# Warble_PitchBird.net
KiCad netlist of a schematic drawn in EAGLE
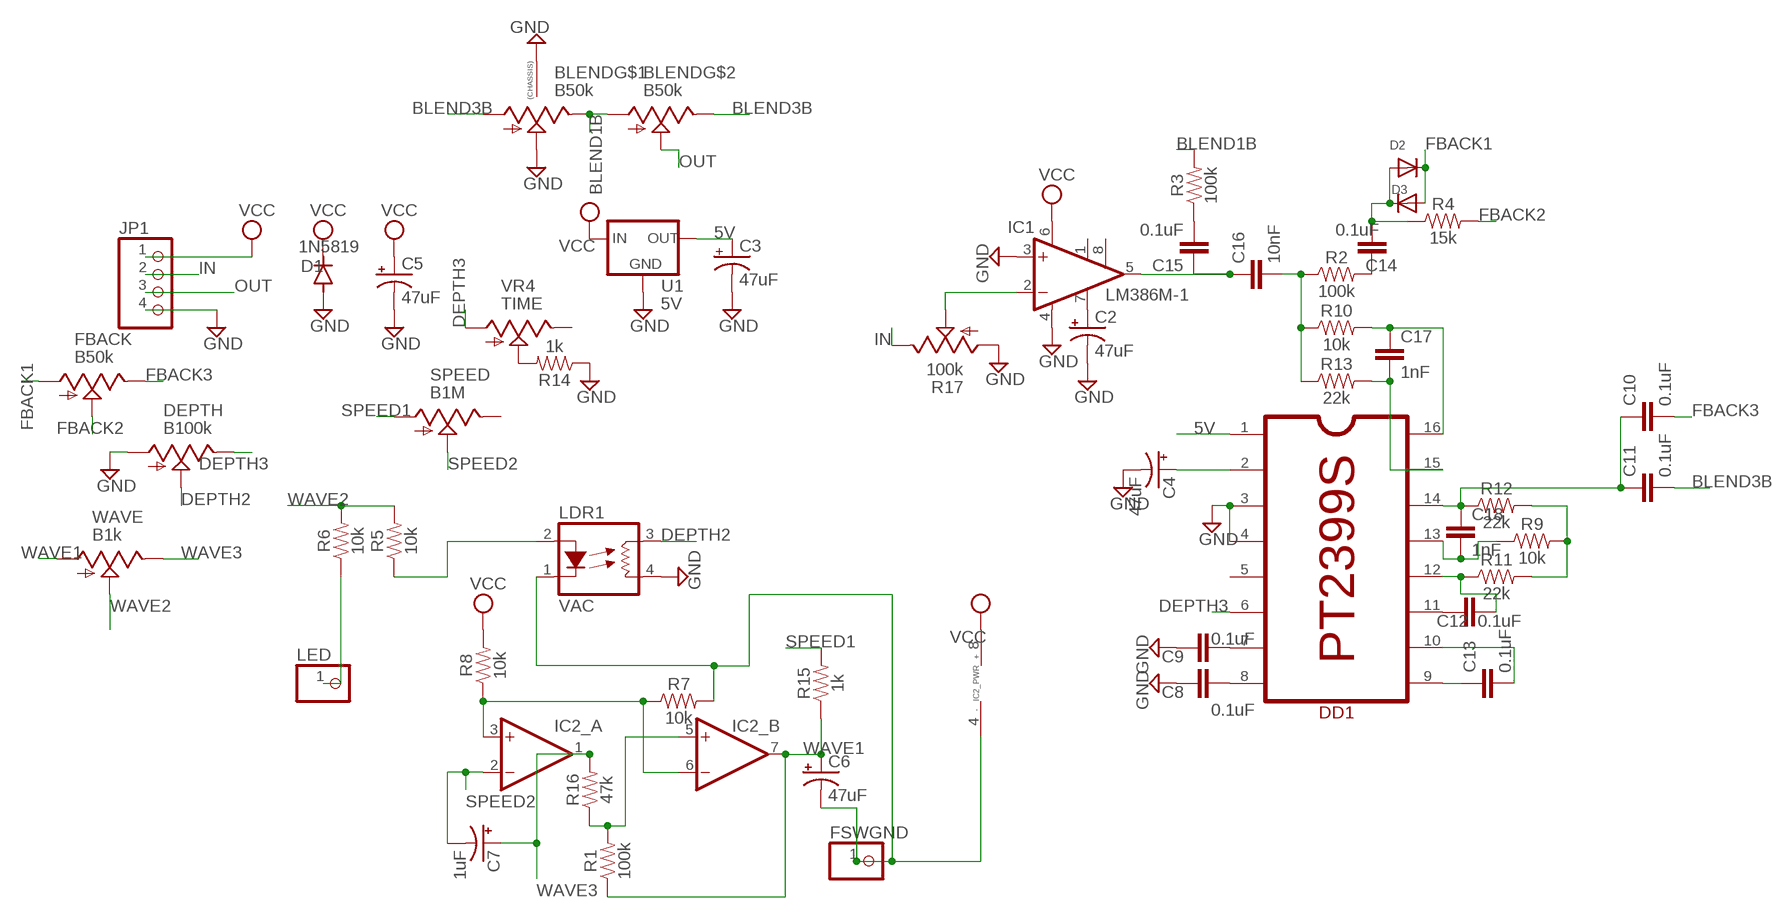
[diagram p0: schematic, sheet 1]

(export (version "E")
  (design (tool "Eeschema 10.0.6"))
  (components
    (comp (ref "BLEND")
      (value "B50k")
      (footprint "eagle-import:DUAL_9MM_SNAP-IN_POT")
      (libsource (lib "eagle-import") (part "ALPHA-9MM-DUALPOT"))
    )
    (comp (ref "C2")
      (value "47uF")
      (footprint "eagle-import:PAN_B_SMD+THRU")
      (libsource (lib "eagle-import") (part "CAP_SMD+THRUPAN_B"))
    )
    (comp (ref "C3")
      (value "47uF")
      (footprint "eagle-import:PAN_B_SMD+THRU")
      (libsource (lib "eagle-import") (part "CAP_SMD+THRUPAN_B"))
    )
    (comp (ref "C4")
      (value "47uF")
      (footprint "eagle-import:PAN_B_SMD+THRU")
      (libsource (lib "eagle-import") (part "CAP_SMD+THRUPAN_B"))
    )
    (comp (ref "C5")
      (value "47uF")
      (footprint "eagle-import:PAN_B_SMD+THRU")
      (libsource (lib "eagle-import") (part "CAP_SMD+THRUPAN_B"))
    )
    (comp (ref "C6")
      (value "47uF")
      (footprint "eagle-import:PAN_B_SMD+THRU")
      (libsource (lib "eagle-import") (part "CAP_SMD+THRUPAN_B"))
    )
    (comp (ref "C7")
      (value "1uF")
      (footprint "eagle-import:PAN_B_SMD+THRU")
      (libsource (lib "eagle-import") (part "CAP_SMD+THRUPAN_B"))
    )
    (comp (ref "C8")
      (value "0.1uF")
      (footprint "eagle-import:0603")
      (libsource (lib "eagle-import") (part "0.1UF-0603-25V-5%"))
    )
    (comp (ref "C9")
      (value "0.1uF")
      (footprint "eagle-import:0603")
      (libsource (lib "eagle-import") (part "0.1UF-0603-25V-5%"))
    )
    (comp (ref "C10")
      (value "0.1uF")
      (footprint "eagle-import:0603")
      (libsource (lib "eagle-import") (part "0.1UF-0603-25V-5%"))
    )
    (comp (ref "C11")
      (value "0.1uF")
      (footprint "eagle-import:0603")
      (libsource (lib "eagle-import") (part "0.1UF-0603-25V-5%"))
    )
    (comp (ref "C12")
      (value "0.1uF")
      (footprint "eagle-import:0603")
      (libsource (lib "eagle-import") (part "0.1UF-0603-25V-5%"))
    )
    (comp (ref "C13")
      (value "0.1uF")
      (footprint "eagle-import:0603")
      (libsource (lib "eagle-import") (part "0.1UF-0603-25V-5%"))
    )
    (comp (ref "C14")
      (value "0.1uF")
      (footprint "eagle-import:0603")
      (libsource (lib "eagle-import") (part "0.1UF-0603-25V-5%"))
    )
    (comp (ref "C15")
      (value "0.1uF")
      (footprint "eagle-import:0603")
      (libsource (lib "eagle-import") (part "0.1UF-0603-25V-5%"))
    )
    (comp (ref "C16")
      (value "10nF")
      (footprint "eagle-import:0603")
      (libsource (lib "eagle-import") (part "10NF-0603-50V-10%"))
    )
    (comp (ref "C17")
      (value "1nF")
      (footprint "eagle-import:0603")
      (libsource (lib "eagle-import") (part "1.0NF/1000PF-0603-50V-10%"))
    )
    (comp (ref "C18")
      (value "1nF")
      (footprint "eagle-import:0603")
      (libsource (lib "eagle-import") (part "1.0NF/1000PF-0603-50V-10%"))
    )
    (comp (ref "D1")
      (value "1N5819")
      (footprint "eagle-import:SOD123")
      (libsource (lib "eagle-import") (part "DIODE-SOD123"))
    )
    (comp (ref "D2")
      (value "DIODESOD-123")
      (footprint "eagle-import:SOD-123")
      (libsource (lib "eagle-import") (part "DIODESOD-123"))
    )
    (comp (ref "D3")
      (value "DIODESOD-123")
      (footprint "eagle-import:SOD-123")
      (libsource (lib "eagle-import") (part "DIODESOD-123"))
    )
    (comp (ref "DD1")
      (value "PT2399S")
      (footprint "eagle-import:SO-16")
      (libsource (lib "eagle-import") (part "PT2399S"))
    )
    (comp (ref "DEPTH")
      (value "B100k")
      (footprint "eagle-import:9MM_SNAP-IN_POT")
      (libsource (lib "eagle-import") (part "9MM_SNAP-IN_POT_"))
    )
    (comp (ref "FBACK")
      (value "B50k")
      (footprint "eagle-import:9MM_SNAP-IN_POT")
      (libsource (lib "eagle-import") (part "9MM_SNAP-IN_POT_"))
    )
    (comp (ref "FSWGND")
      (value "PINHD-1X1")
      (footprint "eagle-import:1X01")
      (libsource (lib "eagle-import") (part "PINHD-1X1"))
    )
    (comp (ref "IC1")
      (value "LM386M-1")
      (footprint "eagle-import:SO08")
      (libsource (lib "eagle-import") (part "LM386?-M1"))
    )
    (comp (ref "IC2")
      (value "DUALSMD")
      (footprint "eagle-import:SO08")
      (libsource (lib "eagle-import") (part "DUALSMD"))
    )
    (comp (ref "JP1")
      (value "PINHD-1X4")
      (footprint "eagle-import:1X04")
      (libsource (lib "eagle-import") (part "PINHD-1X4"))
    )
    (comp (ref "LDR1")
      (value "VAC")
      (footprint "eagle-import:VACTROL_4PIN_VTL5C")
      (libsource (lib "eagle-import") (part "VACTROL_4PIN"))
    )
    (comp (ref "LED")
      (value "PINHD-1X1")
      (footprint "eagle-import:1X01")
      (libsource (lib "eagle-import") (part "PINHD-1X1"))
    )
    (comp (ref "R1")
      (value "100k")
      (footprint "eagle-import:0603")
      (libsource (lib "eagle-import") (part "100KOHM-0603-1/10W-1%"))
    )
    (comp (ref "R2")
      (value "100k")
      (footprint "eagle-import:0603")
      (libsource (lib "eagle-import") (part "100KOHM-0603-1/10W-1%"))
    )
    (comp (ref "R3")
      (value "100k")
      (footprint "eagle-import:0603")
      (libsource (lib "eagle-import") (part "100KOHM-0603-1/10W-1%"))
    )
    (comp (ref "R4")
      (value "15k")
      (footprint "eagle-import:0603")
      (libsource (lib "eagle-import") (part "15KOHM-0603-1/10W-1%"))
    )
    (comp (ref "R5")
      (value "10k")
      (footprint "eagle-import:0603")
      (libsource (lib "eagle-import") (part "10KOHM-0603-1/10W-1%"))
    )
    (comp (ref "R6")
      (value "10k")
      (footprint "eagle-import:0603")
      (libsource (lib "eagle-import") (part "10KOHM-0603-1/10W-1%"))
    )
    (comp (ref "R7")
      (value "10k")
      (footprint "eagle-import:0603")
      (libsource (lib "eagle-import") (part "10KOHM-0603-1/10W-1%"))
    )
    (comp (ref "R8")
      (value "10k")
      (footprint "eagle-import:0603")
      (libsource (lib "eagle-import") (part "10KOHM-0603-1/10W-1%"))
    )
    (comp (ref "R9")
      (value "10k")
      (footprint "eagle-import:0603")
      (libsource (lib "eagle-import") (part "10KOHM-0603-1/10W-1%"))
    )
    (comp (ref "R10")
      (value "10k")
      (footprint "eagle-import:0603")
      (libsource (lib "eagle-import") (part "10KOHM-0603-1/10W-1%"))
    )
    (comp (ref "R11")
      (value "22k")
      (footprint "eagle-import:0603")
      (libsource (lib "eagle-import") (part "22KOHM-0603-1/10W-1%"))
    )
    (comp (ref "R12")
      (value "22k")
      (footprint "eagle-import:0603")
      (libsource (lib "eagle-import") (part "22KOHM-0603-1/10W-1%"))
    )
    (comp (ref "R13")
      (value "22k")
      (footprint "eagle-import:0603")
      (libsource (lib "eagle-import") (part "22KOHM-0603-1/10W-1%"))
    )
    (comp (ref "R14")
      (value "1k")
      (footprint "eagle-import:0603")
      (libsource (lib "eagle-import") (part "1KOHM-0603-1/10W-1%"))
    )
    (comp (ref "R15")
      (value "1k")
      (footprint "eagle-import:0603")
      (libsource (lib "eagle-import") (part "1KOHM-0603-1/10W-1%"))
    )
    (comp (ref "R16")
      (value "47k")
      (footprint "eagle-import:0603")
      (libsource (lib "eagle-import") (part "47KOHM-0603-1/10W-1%"))
    )
    (comp (ref "R17")
      (value "100k")
      (footprint "eagle-import:PT-10")
      (libsource (lib "eagle-import") (part "TRIM_US-PT10"))
    )
    (comp (ref "SPEED")
      (value "B1M")
      (footprint "eagle-import:9MM_SNAP-IN_POT")
      (libsource (lib "eagle-import") (part "9MM_SNAP-IN_POT_"))
    )
    (comp (ref "U1")
      (value "5V")
      (footprint "eagle-import:TO-252")
      (libsource (lib "eagle-import") (part "V_REG_78XX7812"))
    )
    (comp (ref "VR4")
      (value "TIME")
      (footprint "eagle-import:9MM_SNAP-IN_POT")
      (libsource (lib "eagle-import") (part "9MM_SNAP-IN_POT_"))
    )
    (comp (ref "WAVE")
      (value "B1k")
      (footprint "eagle-import:9MM_SNAP-IN_POT")
      (libsource (lib "eagle-import") (part "9MM_SNAP-IN_POT_"))
    )
  )
  (nets
    (net (code "1") (name "/5V") (class "Default")
      (node (ref "C3") (pin "+") (pinfunction "+_+") (pintype "passive"))
      (node (ref "C3") (pin "++") (pinfunction "+_++") (pintype "passive"))
      (node (ref "DD1") (pin "1") (pinfunction "1_1") (pintype "bidirectional"))
      (node (ref "U1") (pin "2") (pinfunction "OUT_2") (pintype "passive"))
    )
    (net (code "2") (name "/BLEND1B") (class "Default")
      (node (ref "BLEND") (pin "1B") (pinfunction "A_1B") (pintype "passive"))
      (node (ref "BLEND") (pin "3") (pinfunction "E_3") (pintype "passive"))
      (node (ref "R3") (pin "2") (pinfunction "2_2") (pintype "passive"))
    )
    (net (code "3") (name "/BLEND3B") (class "Default")
      (node (ref "BLEND") (pin "1") (pinfunction "A_1") (pintype "passive"))
      (node (ref "BLEND") (pin "3B") (pinfunction "E_3B") (pintype "passive"))
      (node (ref "C11") (pin "2") (pinfunction "2_2") (pintype "passive"))
    )
    (net (code "4") (name "/DEPTH2") (class "Default")
      (node (ref "DEPTH") (pin "2") (pinfunction "S_2") (pintype "passive"))
      (node (ref "LDR1") (pin "3") (pinfunction "RES1_3") (pintype "passive"))
    )
    (net (code "5") (name "/DEPTH3") (class "Default")
      (node (ref "DD1") (pin "6") (pinfunction "6_6") (pintype "bidirectional"))
      (node (ref "DEPTH") (pin "3") (pinfunction "E_3") (pintype "passive"))
      (node (ref "VR4") (pin "1") (pinfunction "A_1") (pintype "passive"))
    )
    (net (code "6") (name "/FBACK1") (class "Default")
      (node (ref "D2") (pin "C") (pinfunction "C_C") (pintype "passive"))
      (node (ref "D3") (pin "A") (pinfunction "A_A") (pintype "passive"))
      (node (ref "FBACK") (pin "1") (pinfunction "A_1") (pintype "passive"))
    )
    (net (code "7") (name "/FBACK2") (class "Default")
      (node (ref "FBACK") (pin "2") (pinfunction "S_2") (pintype "passive"))
      (node (ref "R4") (pin "2") (pinfunction "2_2") (pintype "passive"))
    )
    (net (code "8") (name "/FBACK3") (class "Default")
      (node (ref "C10") (pin "2") (pinfunction "2_2") (pintype "passive"))
      (node (ref "FBACK") (pin "3") (pinfunction "E_3") (pintype "passive"))
    )
    (net (code "9") (name "/IN") (class "Default")
      (node (ref "JP1") (pin "2") (pinfunction "2_2") (pintype "passive"))
      (node (ref "R17") (pin "E") (pinfunction "E_E") (pintype "passive"))
    )
    (net (code "10") (name "/OUT") (class "Default")
      (node (ref "BLEND") (pin "2B") (pinfunction "S_2B") (pintype "passive"))
      (node (ref "JP1") (pin "3") (pinfunction "3_3") (pintype "passive"))
    )
    (net (code "11") (name "/SPEED1") (class "Default")
      (node (ref "R15") (pin "2") (pinfunction "2_2") (pintype "passive"))
      (node (ref "SPEED") (pin "1") (pinfunction "A_1") (pintype "passive"))
    )
    (net (code "12") (name "/SPEED2") (class "Default")
      (node (ref "C7") (pin "-") (pinfunction "-_-") (pintype "passive"))
      (node (ref "C7") (pin "--") (pinfunction "-_--") (pintype "passive"))
      (node (ref "IC2") (pin "2") (pinfunction "-IN_2") (pintype "input"))
      (node (ref "SPEED") (pin "2") (pinfunction "S_2") (pintype "passive"))
    )
    (net (code "13") (name "/WAVE1") (class "Default")
      (node (ref "C6") (pin "+") (pinfunction "+_+") (pintype "passive"))
      (node (ref "C6") (pin "++") (pinfunction "+_++") (pintype "passive"))
      (node (ref "IC2") (pin "7") (pinfunction "OUT_7") (pintype "output"))
      (node (ref "R1") (pin "1") (pinfunction "1_1") (pintype "passive"))
      (node (ref "R15") (pin "1") (pinfunction "1_1") (pintype "passive"))
      (node (ref "WAVE") (pin "1") (pinfunction "A_1") (pintype "passive"))
    )
    (net (code "14") (name "/WAVE2") (class "Default")
      (node (ref "R5") (pin "2") (pinfunction "2_2") (pintype "passive"))
      (node (ref "R6") (pin "2") (pinfunction "2_2") (pintype "passive"))
      (node (ref "WAVE") (pin "2") (pinfunction "S_2") (pintype "passive"))
    )
    (net (code "15") (name "/WAVE3") (class "Default")
      (node (ref "C7") (pin "+") (pinfunction "+_+") (pintype "passive"))
      (node (ref "C7") (pin "++") (pinfunction "+_++") (pintype "passive"))
      (node (ref "IC2") (pin "1") (pinfunction "OUT_1") (pintype "output"))
      (node (ref "R16") (pin "2") (pinfunction "2_2") (pintype "passive"))
      (node (ref "WAVE") (pin "3") (pinfunction "E_3") (pintype "passive"))
    )
    (net (code "16") (name "GND") (class "Default")
      (node (ref "BLEND") (pin "2") (pinfunction "S_2") (pintype "passive"))
      (node (ref "BLEND") (pin "CHASSIS1") (pinfunction "P$1_CHASSIS1") (pintype "passive"))
      (node (ref "BLEND") (pin "CHASSIS2") (pinfunction "P$1_CHASSIS2") (pintype "passive"))
      (node (ref "C2") (pin "-") (pinfunction "-_-") (pintype "passive"))
      (node (ref "C2") (pin "--") (pinfunction "-_--") (pintype "passive"))
      (node (ref "C3") (pin "-") (pinfunction "-_-") (pintype "passive"))
      (node (ref "C3") (pin "--") (pinfunction "-_--") (pintype "passive"))
      (node (ref "C4") (pin "-") (pinfunction "-_-") (pintype "passive"))
      (node (ref "C4") (pin "--") (pinfunction "-_--") (pintype "passive"))
      (node (ref "C5") (pin "-") (pinfunction "-_-") (pintype "passive"))
      (node (ref "C5") (pin "--") (pinfunction "-_--") (pintype "passive"))
      (node (ref "C8") (pin "1") (pinfunction "1_1") (pintype "passive"))
      (node (ref "C9") (pin "1") (pinfunction "1_1") (pintype "passive"))
      (node (ref "D1") (pin "A") (pinfunction "A_A") (pintype "passive"))
      (node (ref "DD1") (pin "3") (pinfunction "3_3") (pintype "bidirectional"))
      (node (ref "DD1") (pin "4") (pinfunction "4_4") (pintype "bidirectional"))
      (node (ref "DEPTH") (pin "1") (pinfunction "A_1") (pintype "passive"))
      (node (ref "IC1") (pin "3") (pinfunction "+IN_3") (pintype "input"))
      (node (ref "IC1") (pin "4") (pinfunction "GND_4") (pintype "power_in"))
      (node (ref "JP1") (pin "4") (pinfunction "4_4") (pintype "passive"))
      (node (ref "LDR1") (pin "4") (pinfunction "RES2_4") (pintype "passive"))
      (node (ref "R14") (pin "1") (pinfunction "1_1") (pintype "passive"))
      (node (ref "R17") (pin "A") (pinfunction "A_A") (pintype "passive"))
      (node (ref "U1") (pin "3") (pinfunction "GND_3") (pintype "input"))
    )
    (net (code "17") (name "Net-(C4-+-Pad++)") (class "Default")
      (node (ref "C4") (pin "+") (pinfunction "+_+") (pintype "passive"))
      (node (ref "C4") (pin "++") (pinfunction "+_++") (pintype "passive"))
      (node (ref "DD1") (pin "2") (pinfunction "2_2") (pintype "bidirectional"))
    )
    (net (code "18") (name "Net-(C8-Pad2)") (class "Default")
      (node (ref "C8") (pin "2") (pinfunction "2_2") (pintype "passive"))
      (node (ref "DD1") (pin "8") (pinfunction "8_8") (pintype "bidirectional"))
    )
    (net (code "19") (name "Net-(C9-Pad2)") (class "Default")
      (node (ref "C9") (pin "2") (pinfunction "2_2") (pintype "passive"))
      (node (ref "DD1") (pin "7") (pinfunction "7_7") (pintype "bidirectional"))
    )
    (net (code "20") (name "Net-(C10-Pad1)") (class "Default")
      (node (ref "C10") (pin "1") (pinfunction "1_1") (pintype "passive"))
      (node (ref "C11") (pin "1") (pinfunction "1_1") (pintype "passive"))
      (node (ref "C18") (pin "1") (pinfunction "1_1") (pintype "passive"))
      (node (ref "DD1") (pin "14") (pinfunction "14_14") (pintype "bidirectional"))
      (node (ref "R12") (pin "1") (pinfunction "1_1") (pintype "passive"))
    )
    (net (code "21") (name "Net-(C12-Pad1)") (class "Default")
      (node (ref "C12") (pin "1") (pinfunction "1_1") (pintype "passive"))
      (node (ref "DD1") (pin "11") (pinfunction "11_11") (pintype "bidirectional"))
    )
    (net (code "22") (name "Net-(C12-Pad2)") (class "Default")
      (node (ref "C12") (pin "2") (pinfunction "2_2") (pintype "passive"))
      (node (ref "DD1") (pin "12") (pinfunction "12_12") (pintype "bidirectional"))
      (node (ref "R11") (pin "1") (pinfunction "1_1") (pintype "passive"))
    )
    (net (code "23") (name "Net-(C13-Pad1)") (class "Default")
      (node (ref "C13") (pin "1") (pinfunction "1_1") (pintype "passive"))
      (node (ref "DD1") (pin "9") (pinfunction "9_9") (pintype "bidirectional"))
    )
    (net (code "24") (name "Net-(C13-Pad2)") (class "Default")
      (node (ref "C13") (pin "2") (pinfunction "2_2") (pintype "passive"))
      (node (ref "DD1") (pin "10") (pinfunction "10_10") (pintype "bidirectional"))
    )
    (net (code "25") (name "Net-(C14-Pad1)") (class "Default")
      (node (ref "C14") (pin "1") (pinfunction "1_1") (pintype "passive"))
      (node (ref "R2") (pin "2") (pinfunction "2_2") (pintype "passive"))
    )
    (net (code "26") (name "Net-(C14-Pad2)") (class "Default")
      (node (ref "C14") (pin "2") (pinfunction "2_2") (pintype "passive"))
      (node (ref "D2") (pin "A") (pinfunction "A_A") (pintype "passive"))
      (node (ref "D3") (pin "C") (pinfunction "C_C") (pintype "passive"))
      (node (ref "R4") (pin "1") (pinfunction "1_1") (pintype "passive"))
    )
    (net (code "27") (name "Net-(C15-Pad2)") (class "Default")
      (node (ref "C15") (pin "2") (pinfunction "2_2") (pintype "passive"))
      (node (ref "R3") (pin "1") (pinfunction "1_1") (pintype "passive"))
    )
    (net (code "28") (name "Net-(C16-Pad2)") (class "Default")
      (node (ref "C16") (pin "2") (pinfunction "2_2") (pintype "passive"))
      (node (ref "R10") (pin "1") (pinfunction "1_1") (pintype "passive"))
      (node (ref "R13") (pin "1") (pinfunction "1_1") (pintype "passive"))
      (node (ref "R2") (pin "1") (pinfunction "1_1") (pintype "passive"))
    )
    (net (code "29") (name "Net-(C17-Pad1)") (class "Default")
      (node (ref "C17") (pin "1") (pinfunction "1_1") (pintype "passive"))
      (node (ref "DD1") (pin "16") (pinfunction "16_16") (pintype "bidirectional"))
      (node (ref "R10") (pin "2") (pinfunction "2_2") (pintype "passive"))
    )
    (net (code "30") (name "Net-(C17-Pad2)") (class "Default")
      (node (ref "C17") (pin "2") (pinfunction "2_2") (pintype "passive"))
      (node (ref "DD1") (pin "15") (pinfunction "15_15") (pintype "bidirectional"))
      (node (ref "R13") (pin "2") (pinfunction "2_2") (pintype "passive"))
    )
    (net (code "31") (name "Net-(C18-Pad2)") (class "Default")
      (node (ref "C18") (pin "2") (pinfunction "2_2") (pintype "passive"))
      (node (ref "DD1") (pin "13") (pinfunction "13_13") (pintype "bidirectional"))
      (node (ref "R9") (pin "1") (pinfunction "1_1") (pintype "passive"))
    )
    (net (code "32") (name "Net-(IC1--IN)") (class "Default")
      (node (ref "IC1") (pin "2") (pinfunction "-IN_2") (pintype "input"))
      (node (ref "R17") (pin "S") (pinfunction "S_S") (pintype "passive"))
    )
    (net (code "33") (name "Net-(IC1-BYPASS)") (class "Default")
      (node (ref "C2") (pin "+") (pinfunction "+_+") (pintype "passive"))
      (node (ref "C2") (pin "++") (pinfunction "+_++") (pintype "passive"))
      (node (ref "IC1") (pin "7") (pinfunction "BYPASS_7") (pintype "passive"))
    )
    (net (code "34") (name "Net-(IC1-OUT)") (class "Default")
      (node (ref "C15") (pin "1") (pinfunction "1_1") (pintype "passive"))
      (node (ref "C16") (pin "1") (pinfunction "1_1") (pintype "passive"))
      (node (ref "IC1") (pin "5") (pinfunction "OUT_5") (pintype "output"))
    )
    (net (code "35") (name "Net-(IC2A-+IN)") (class "Default")
      (node (ref "IC2") (pin "3") (pinfunction "+IN_3") (pintype "input"))
      (node (ref "IC2") (pin "6") (pinfunction "-IN_6") (pintype "input"))
      (node (ref "R7") (pin "1") (pinfunction "1_1") (pintype "passive"))
      (node (ref "R8") (pin "1") (pinfunction "1_1") (pintype "passive"))
    )
    (net (code "36") (name "Net-(IC2B-+IN)") (class "Default")
      (node (ref "IC2") (pin "5") (pinfunction "+IN_5") (pintype "input"))
      (node (ref "R1") (pin "2") (pinfunction "2_2") (pintype "passive"))
      (node (ref "R16") (pin "1") (pinfunction "1_1") (pintype "passive"))
    )
    (net (code "37") (name "Net-(IC2C-V-)") (class "Default")
      (node (ref "C6") (pin "-") (pinfunction "-_-") (pintype "passive"))
      (node (ref "C6") (pin "--") (pinfunction "-_--") (pintype "passive"))
      (node (ref "FSWGND") (pin "1") (pinfunction "1_1") (pintype "passive"))
      (node (ref "IC2") (pin "4") (pinfunction "V-_4") (pintype "power_in"))
      (node (ref "LDR1") (pin "1") (pinfunction "LED-_1") (pintype "passive"))
      (node (ref "R7") (pin "2") (pinfunction "2_2") (pintype "passive"))
    )
    (net (code "38") (name "Net-(LDR1-LED+)") (class "Default")
      (node (ref "LDR1") (pin "2") (pinfunction "LED+_2") (pintype "passive"))
      (node (ref "R5") (pin "1") (pinfunction "1_1") (pintype "passive"))
    )
    (net (code "39") (name "Net-(LED-Pad1)") (class "Default")
      (node (ref "LED") (pin "1") (pinfunction "1_1") (pintype "passive"))
      (node (ref "R6") (pin "1") (pinfunction "1_1") (pintype "passive"))
    )
    (net (code "40") (name "Net-(R11-Pad2)") (class "Default")
      (node (ref "R11") (pin "2") (pinfunction "2_2") (pintype "passive"))
      (node (ref "R12") (pin "2") (pinfunction "2_2") (pintype "passive"))
      (node (ref "R9") (pin "2") (pinfunction "2_2") (pintype "passive"))
    )
    (net (code "41") (name "Net-(VR4-S)") (class "Default")
      (node (ref "R14") (pin "2") (pinfunction "2_2") (pintype "passive"))
      (node (ref "VR4") (pin "2") (pinfunction "S_2") (pintype "passive"))
    )
    (net (code "42") (name "VCC") (class "Default")
      (node (ref "C5") (pin "+") (pinfunction "+_+") (pintype "passive"))
      (node (ref "C5") (pin "++") (pinfunction "+_++") (pintype "passive"))
      (node (ref "D1") (pin "C") (pinfunction "C_C") (pintype "passive"))
      (node (ref "IC1") (pin "6") (pinfunction "VS_6") (pintype "power_in"))
      (node (ref "IC2") (pin "8") (pinfunction "V+_8") (pintype "power_in"))
      (node (ref "JP1") (pin "1") (pinfunction "1_1") (pintype "passive"))
      (node (ref "R8") (pin "2") (pinfunction "2_2") (pintype "passive"))
      (node (ref "U1") (pin "1") (pinfunction "IN_1") (pintype "input"))
    )
    (net (code "43") (name "unconnected-(DD1-Pad5)") (class "Default")
      (node (ref "DD1") (pin "5") (pinfunction "5_5") (pintype "bidirectional"))
    )
    (net (code "44") (name "unconnected-(IC1-GAIN-Pad1)") (class "Default")
      (node (ref "IC1") (pin "1") (pinfunction "GAIN_1") (pintype "passive"))
    )
    (net (code "45") (name "unconnected-(IC1-GAIN-Pad8)") (class "Default")
      (node (ref "IC1") (pin "8") (pinfunction "GAIN_8") (pintype "passive"))
    )
    (net (code "46") (name "unconnected-(SPEED-E-Pad3)") (class "Default")
      (node (ref "SPEED") (pin "3") (pinfunction "E_3") (pintype "passive"))
    )
    (net (code "47") (name "unconnected-(VR4-E-Pad3)") (class "Default")
      (node (ref "VR4") (pin "3") (pinfunction "E_3") (pintype "passive"))
    )
  )
)
